# bitfury_10_1403.net
KiCad netlist of a schematic drawn in EAGLE
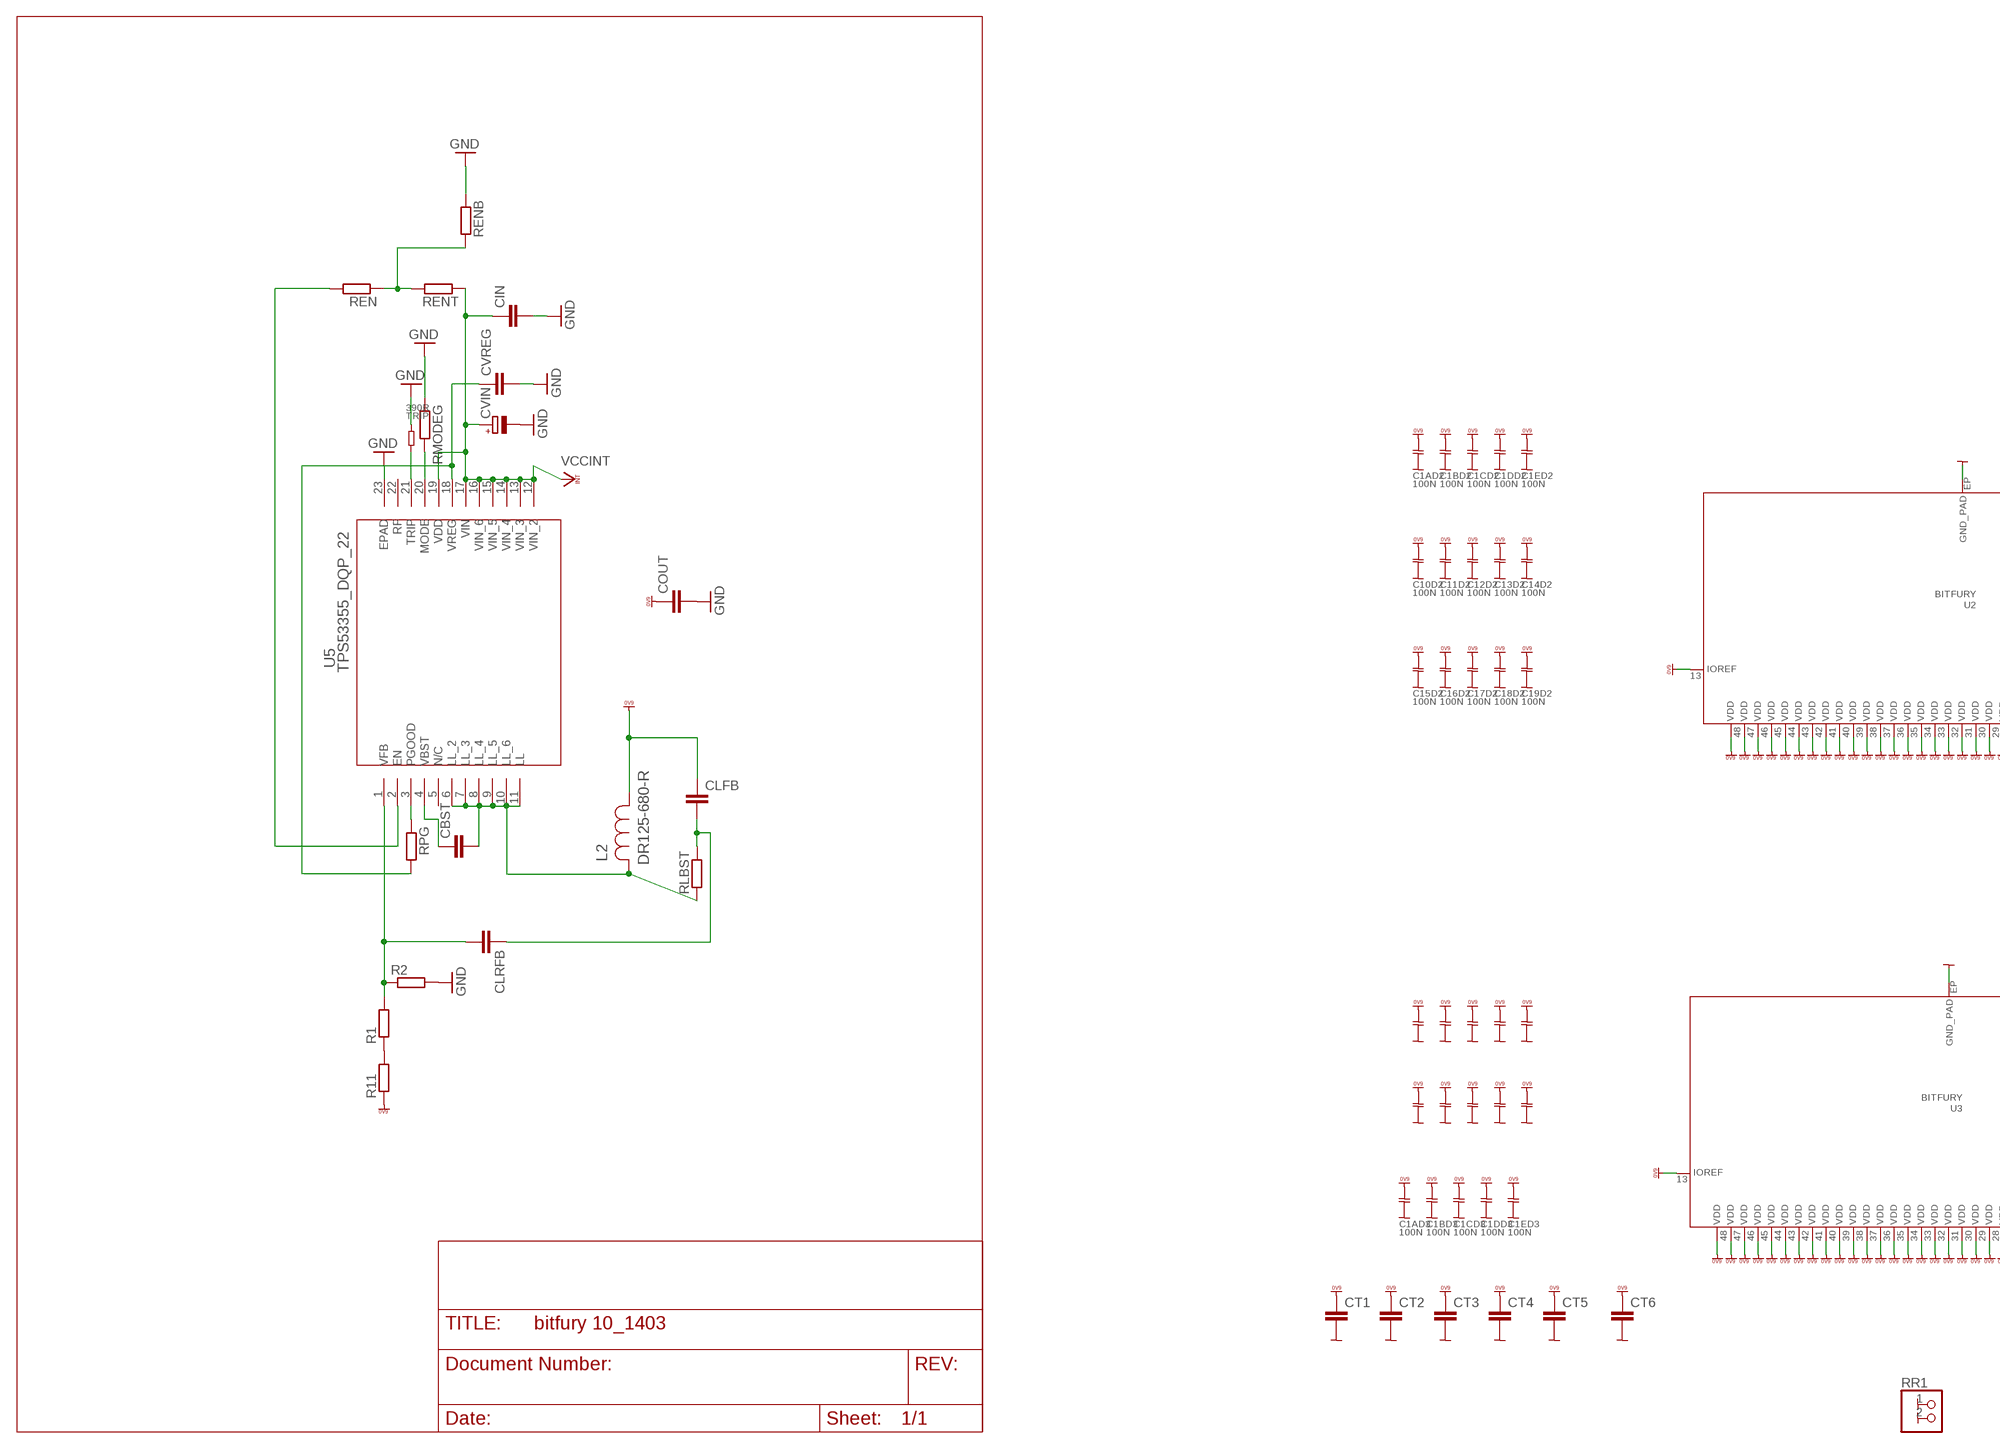
[diagram p0: schematic, sheet 1, part 1 of 3]
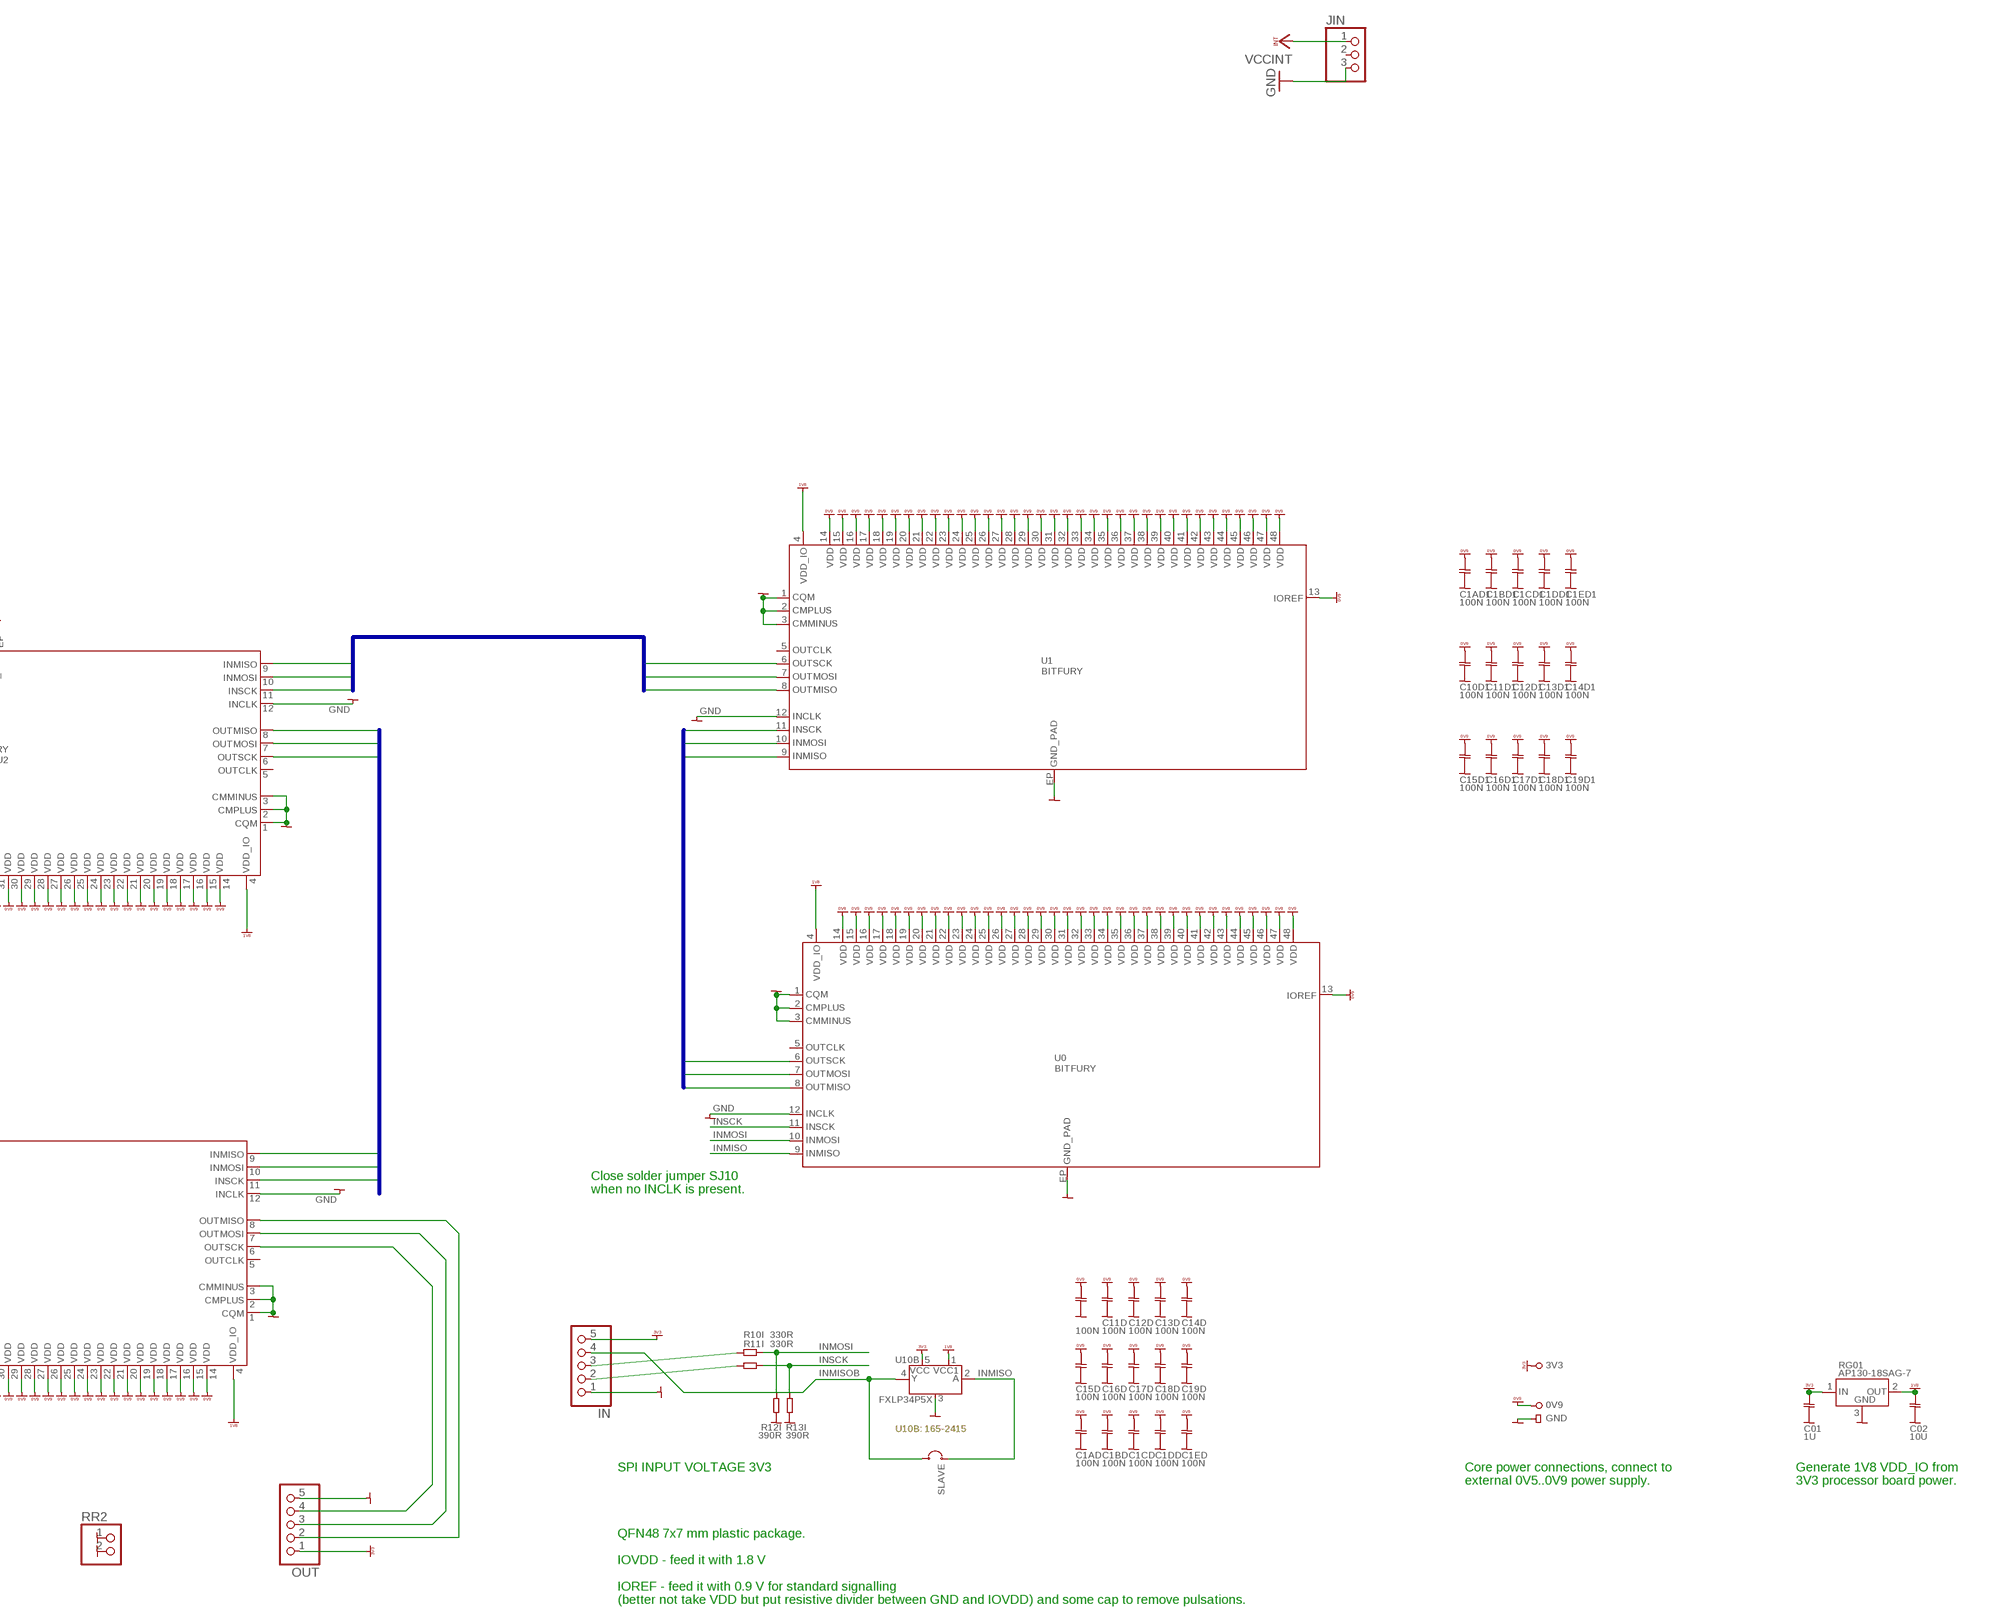
[diagram p1: schematic, sheet 1, part 2 of 3]
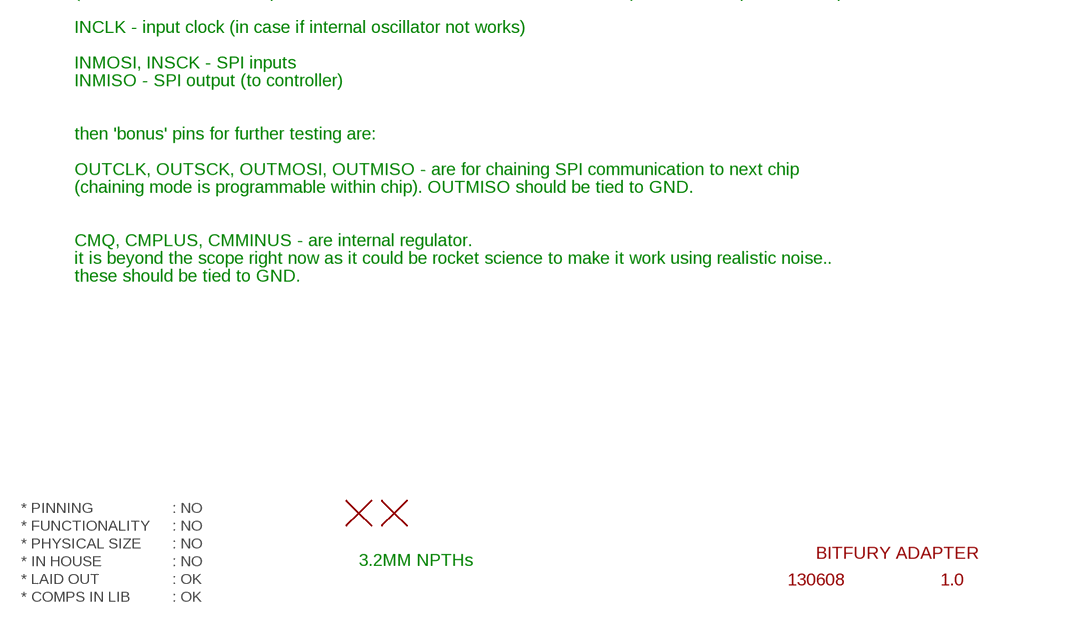
[diagram p2: schematic, sheet 1, part 3 of 3]

(export (version "E")
  (design (tool "Eeschema 10.0.6"))
  (components
    (comp (ref "0V9")
      (value "PIN_TEST_BIG")
      (footprint "eagle-import:PAD_HOLE_BIG")
      (libsource (lib "eagle-import") (part "PIN_TEST_BIG"))
    )
    (comp (ref "3V3")
      (value "PIN_TEST_BIG")
      (footprint "eagle-import:PAD_HOLE_BIG")
      (libsource (lib "eagle-import") (part "PIN_TEST_BIG"))
    )
    (comp (ref "C01")
      (value "1U")
      (footprint "eagle-import:CAP0603")
      (libsource (lib "eagle-import") (part "CAP0603"))
    )
    (comp (ref "C1AD")
      (value "100N")
      (footprint "eagle-import:CAP0402")
      (libsource (lib "eagle-import") (part "CAP0402"))
    )
    (comp (ref "C1AD1")
      (value "100N")
      (footprint "eagle-import:CAP0402")
      (libsource (lib "eagle-import") (part "CAP0402"))
    )
    (comp (ref "C1AD2")
      (value "100N")
      (footprint "eagle-import:CAP0402")
      (libsource (lib "eagle-import") (part "CAP0402"))
    )
    (comp (ref "C1AD3")
      (value "100N")
      (footprint "eagle-import:CAP0402")
      (libsource (lib "eagle-import") (part "CAP0402"))
    )
    (comp (ref "C1BD")
      (value "100N")
      (footprint "eagle-import:CAP0402")
      (libsource (lib "eagle-import") (part "CAP0402"))
    )
    (comp (ref "C1BD1")
      (value "100N")
      (footprint "eagle-import:CAP0402")
      (libsource (lib "eagle-import") (part "CAP0402"))
    )
    (comp (ref "C1BD2")
      (value "100N")
      (footprint "eagle-import:CAP0402")
      (libsource (lib "eagle-import") (part "CAP0402"))
    )
    (comp (ref "C1BD3")
      (value "100N")
      (footprint "eagle-import:CAP0402")
      (libsource (lib "eagle-import") (part "CAP0402"))
    )
    (comp (ref "C1CD")
      (value "100N")
      (footprint "eagle-import:CAP0402")
      (libsource (lib "eagle-import") (part "CAP0402"))
    )
    (comp (ref "C1CD1")
      (value "100N")
      (footprint "eagle-import:CAP0402")
      (libsource (lib "eagle-import") (part "CAP0402"))
    )
    (comp (ref "C1CD2")
      (value "100N")
      (footprint "eagle-import:CAP0402")
      (libsource (lib "eagle-import") (part "CAP0402"))
    )
    (comp (ref "C1CD3")
      (value "100N")
      (footprint "eagle-import:CAP0402")
      (libsource (lib "eagle-import") (part "CAP0402"))
    )
    (comp (ref "C1DD")
      (value "100N")
      (footprint "eagle-import:CAP0402")
      (libsource (lib "eagle-import") (part "CAP0402"))
    )
    (comp (ref "C1DD1")
      (value "100N")
      (footprint "eagle-import:CAP0402")
      (libsource (lib "eagle-import") (part "CAP0402"))
    )
    (comp (ref "C1DD2")
      (value "100N")
      (footprint "eagle-import:CAP0402")
      (libsource (lib "eagle-import") (part "CAP0402"))
    )
    (comp (ref "C1DD3")
      (value "100N")
      (footprint "eagle-import:CAP0402")
      (libsource (lib "eagle-import") (part "CAP0402"))
    )
    (comp (ref "C1ED")
      (value "100N")
      (footprint "eagle-import:CAP0402")
      (libsource (lib "eagle-import") (part "CAP0402"))
    )
    (comp (ref "C1ED1")
      (value "100N")
      (footprint "eagle-import:CAP0402")
      (libsource (lib "eagle-import") (part "CAP0402"))
    )
    (comp (ref "C1ED2")
      (value "100N")
      (footprint "eagle-import:CAP0402")
      (libsource (lib "eagle-import") (part "CAP0402"))
    )
    (comp (ref "C1ED3")
      (value "100N")
      (footprint "eagle-import:CAP0402")
      (libsource (lib "eagle-import") (part "CAP0402"))
    )
    (comp (ref "C02")
      (value "10U")
      (footprint "eagle-import:CAP0603")
      (libsource (lib "eagle-import") (part "CAP0603"))
    )
    (comp (ref "C10D")
      (value "100N")
      (footprint "eagle-import:CAP0402")
      (libsource (lib "eagle-import") (part "CAP0402"))
    )
    (comp (ref "C10D1")
      (value "100N")
      (footprint "eagle-import:CAP0402")
      (libsource (lib "eagle-import") (part "CAP0402"))
    )
    (comp (ref "C10D2")
      (value "100N")
      (footprint "eagle-import:CAP0402")
      (libsource (lib "eagle-import") (part "CAP0402"))
    )
    (comp (ref "C10D3")
      (value "100N")
      (footprint "eagle-import:CAP0402")
      (libsource (lib "eagle-import") (part "CAP0402"))
    )
    (comp (ref "C11D")
      (value "100N")
      (footprint "eagle-import:CAP0402")
      (libsource (lib "eagle-import") (part "CAP0402"))
    )
    (comp (ref "C11D1")
      (value "100N")
      (footprint "eagle-import:CAP0402")
      (libsource (lib "eagle-import") (part "CAP0402"))
    )
    (comp (ref "C11D2")
      (value "100N")
      (footprint "eagle-import:CAP0402")
      (libsource (lib "eagle-import") (part "CAP0402"))
    )
    (comp (ref "C11D3")
      (value "100N")
      (footprint "eagle-import:CAP0402")
      (libsource (lib "eagle-import") (part "CAP0402"))
    )
    (comp (ref "C12D")
      (value "100N")
      (footprint "eagle-import:CAP0402")
      (libsource (lib "eagle-import") (part "CAP0402"))
    )
    (comp (ref "C12D1")
      (value "100N")
      (footprint "eagle-import:CAP0402")
      (libsource (lib "eagle-import") (part "CAP0402"))
    )
    (comp (ref "C12D2")
      (value "100N")
      (footprint "eagle-import:CAP0402")
      (libsource (lib "eagle-import") (part "CAP0402"))
    )
    (comp (ref "C12D3")
      (value "100N")
      (footprint "eagle-import:CAP0402")
      (libsource (lib "eagle-import") (part "CAP0402"))
    )
    (comp (ref "C13D")
      (value "100N")
      (footprint "eagle-import:CAP0402")
      (libsource (lib "eagle-import") (part "CAP0402"))
    )
    (comp (ref "C13D1")
      (value "100N")
      (footprint "eagle-import:CAP0402")
      (libsource (lib "eagle-import") (part "CAP0402"))
    )
    (comp (ref "C13D2")
      (value "100N")
      (footprint "eagle-import:CAP0402")
      (libsource (lib "eagle-import") (part "CAP0402"))
    )
    (comp (ref "C13D3")
      (value "100N")
      (footprint "eagle-import:CAP0402")
      (libsource (lib "eagle-import") (part "CAP0402"))
    )
    (comp (ref "C14D")
      (value "100N")
      (footprint "eagle-import:CAP0402")
      (libsource (lib "eagle-import") (part "CAP0402"))
    )
    (comp (ref "C14D1")
      (value "100N")
      (footprint "eagle-import:CAP0402")
      (libsource (lib "eagle-import") (part "CAP0402"))
    )
    (comp (ref "C14D2")
      (value "100N")
      (footprint "eagle-import:CAP0402")
      (libsource (lib "eagle-import") (part "CAP0402"))
    )
    (comp (ref "C14D3")
      (value "100N")
      (footprint "eagle-import:CAP0402")
      (libsource (lib "eagle-import") (part "CAP0402"))
    )
    (comp (ref "C15D")
      (value "100N")
      (footprint "eagle-import:CAP0402")
      (libsource (lib "eagle-import") (part "CAP0402"))
    )
    (comp (ref "C15D1")
      (value "100N")
      (footprint "eagle-import:CAP0402")
      (libsource (lib "eagle-import") (part "CAP0402"))
    )
    (comp (ref "C15D2")
      (value "100N")
      (footprint "eagle-import:CAP0402")
      (libsource (lib "eagle-import") (part "CAP0402"))
    )
    (comp (ref "C15D3")
      (value "100N")
      (footprint "eagle-import:CAP0402")
      (libsource (lib "eagle-import") (part "CAP0402"))
    )
    (comp (ref "C16D")
      (value "100N")
      (footprint "eagle-import:CAP0402")
      (libsource (lib "eagle-import") (part "CAP0402"))
    )
    (comp (ref "C16D1")
      (value "100N")
      (footprint "eagle-import:CAP0402")
      (libsource (lib "eagle-import") (part "CAP0402"))
    )
    (comp (ref "C16D2")
      (value "100N")
      (footprint "eagle-import:CAP0402")
      (libsource (lib "eagle-import") (part "CAP0402"))
    )
    (comp (ref "C16D3")
      (value "100N")
      (footprint "eagle-import:CAP0402")
      (libsource (lib "eagle-import") (part "CAP0402"))
    )
    (comp (ref "C17D")
      (value "100N")
      (footprint "eagle-import:CAP0402")
      (libsource (lib "eagle-import") (part "CAP0402"))
    )
    (comp (ref "C17D1")
      (value "100N")
      (footprint "eagle-import:CAP0402")
      (libsource (lib "eagle-import") (part "CAP0402"))
    )
    (comp (ref "C17D2")
      (value "100N")
      (footprint "eagle-import:CAP0402")
      (libsource (lib "eagle-import") (part "CAP0402"))
    )
    (comp (ref "C17D3")
      (value "100N")
      (footprint "eagle-import:CAP0402")
      (libsource (lib "eagle-import") (part "CAP0402"))
    )
    (comp (ref "C18D")
      (value "100N")
      (footprint "eagle-import:CAP0402")
      (libsource (lib "eagle-import") (part "CAP0402"))
    )
    (comp (ref "C18D1")
      (value "100N")
      (footprint "eagle-import:CAP0402")
      (libsource (lib "eagle-import") (part "CAP0402"))
    )
    (comp (ref "C18D2")
      (value "100N")
      (footprint "eagle-import:CAP0402")
      (libsource (lib "eagle-import") (part "CAP0402"))
    )
    (comp (ref "C18D3")
      (value "100N")
      (footprint "eagle-import:CAP0402")
      (libsource (lib "eagle-import") (part "CAP0402"))
    )
    (comp (ref "C19D")
      (value "100N")
      (footprint "eagle-import:CAP0402")
      (libsource (lib "eagle-import") (part "CAP0402"))
    )
    (comp (ref "C19D1")
      (value "100N")
      (footprint "eagle-import:CAP0402")
      (libsource (lib "eagle-import") (part "CAP0402"))
    )
    (comp (ref "C19D2")
      (value "100N")
      (footprint "eagle-import:CAP0402")
      (libsource (lib "eagle-import") (part "CAP0402"))
    )
    (comp (ref "C19D3")
      (value "100N")
      (footprint "eagle-import:CAP0402")
      (libsource (lib "eagle-import") (part "CAP0402"))
    )
    (comp (ref "CBST")
      (value "C-EUC0805")
      (footprint "eagle-import:C0805")
      (libsource (lib "eagle-import") (part "C-EUC0805"))
    )
    (comp (ref "CIN")
      (value "C-EUC1210")
      (footprint "eagle-import:C1210")
      (libsource (lib "eagle-import") (part "C-EUC1210"))
    )
    (comp (ref "CLFB")
      (value "C-EUC0805")
      (footprint "eagle-import:C0805")
      (libsource (lib "eagle-import") (part "C-EUC0805"))
    )
    (comp (ref "CLRFB")
      (value "C-EUC0805")
      (footprint "eagle-import:C0805")
      (libsource (lib "eagle-import") (part "C-EUC0805"))
    )
    (comp (ref "COUT")
      (value "C-EUC1210")
      (footprint "eagle-import:C1210")
      (libsource (lib "eagle-import") (part "C-EUC1210"))
    )
    (comp (ref "CT1")
      (value "C-EUC1206")
      (footprint "eagle-import:C1206")
      (libsource (lib "eagle-import") (part "C-EUC1206"))
    )
    (comp (ref "CT2")
      (value "C-EUC1206")
      (footprint "eagle-import:C1206")
      (libsource (lib "eagle-import") (part "C-EUC1206"))
    )
    (comp (ref "CT3")
      (value "C-EUC1206")
      (footprint "eagle-import:C1206")
      (libsource (lib "eagle-import") (part "C-EUC1206"))
    )
    (comp (ref "CT4")
      (value "C-EUC1206")
      (footprint "eagle-import:C1206")
      (libsource (lib "eagle-import") (part "C-EUC1206"))
    )
    (comp (ref "CT5")
      (value "C-EUC1206")
      (footprint "eagle-import:C1206")
      (libsource (lib "eagle-import") (part "C-EUC1206"))
    )
    (comp (ref "CT6")
      (value "C-EUC1206")
      (footprint "eagle-import:C1206")
      (libsource (lib "eagle-import") (part "C-EUC1206"))
    )
    (comp (ref "CVIN")
      (value "CPOL-EU153CLV-0505")
      (footprint "eagle-import:153CLV-0505")
      (libsource (lib "eagle-import") (part "CPOL-EU153CLV-0505"))
    )
    (comp (ref "CVREG")
      (value "C-EUC0603")
      (footprint "eagle-import:C0603")
      (libsource (lib "eagle-import") (part "C-EUC0603"))
    )
    (comp (ref "H1")
      (value "HOLE_NPTH_3.2MM")
      (footprint "eagle-import:HOLE_NPTH_3.2MM")
      (libsource (lib "eagle-import") (part "HOLE_NPTH_3.2MM"))
    )
    (comp (ref "H2")
      (value "HOLE_NPTH_3.2MM")
      (footprint "eagle-import:HOLE_NPTH_3.2MM")
      (libsource (lib "eagle-import") (part "HOLE_NPTH_3.2MM"))
    )
    (comp (ref "IN")
      (value "PINHD-1X5/90")
      (footprint "eagle-import:1X05_90")
      (libsource (lib "eagle-import") (part "PINHD-1X5/90"))
    )
    (comp (ref "JIN")
      (value "PINHD-1X3")
      (footprint "eagle-import:1X03")
      (libsource (lib "eagle-import") (part "PINHD-1X3"))
    )
    (comp (ref "L2")
      (value "DR125-680-R")
      (footprint "eagle-import:INDM125125X600N")
      (fields (field (name "TOLERANCE") "±20%"))
      (libsource (lib "eagle-import") (part "DR125-680-R"))
    )
    (comp (ref "OUT")
      (value "PINHD-1X5/90")
      (footprint "eagle-import:1X05_90")
      (libsource (lib "eagle-import") (part "PINHD-1X5/90"))
    )
    (comp (ref "R1")
      (value "R-EU_R0603")
      (footprint "eagle-import:R0603")
      (libsource (lib "eagle-import") (part "R-EU_R0603"))
    )
    (comp (ref "R2")
      (value "R-EU_R0603")
      (footprint "eagle-import:R0603")
      (libsource (lib "eagle-import") (part "R-EU_R0603"))
    )
    (comp (ref "R10I")
      (value "330R")
      (footprint "eagle-import:RES0603")
      (libsource (lib "eagle-import") (part "RES0603"))
    )
    (comp (ref "R11")
      (value "R-EU_R0603")
      (footprint "eagle-import:R0603")
      (libsource (lib "eagle-import") (part "R-EU_R0603"))
    )
    (comp (ref "R11I")
      (value "330R")
      (footprint "eagle-import:RES0603")
      (libsource (lib "eagle-import") (part "RES0603"))
    )
    (comp (ref "R12I")
      (value "390R")
      (footprint "eagle-import:RES0603")
      (libsource (lib "eagle-import") (part "RES0603"))
    )
    (comp (ref "R13I")
      (value "390R")
      (footprint "eagle-import:RES0603")
      (libsource (lib "eagle-import") (part "RES0603"))
    )
    (comp (ref "REN")
      (value "R-EU_R0603")
      (footprint "eagle-import:R0603")
      (libsource (lib "eagle-import") (part "R-EU_R0603"))
    )
    (comp (ref "RENB")
      (value "R-EU_R0603")
      (footprint "eagle-import:R0603")
      (libsource (lib "eagle-import") (part "R-EU_R0603"))
    )
    (comp (ref "RENT")
      (value "R-EU_R0603")
      (footprint "eagle-import:R0603")
      (libsource (lib "eagle-import") (part "R-EU_R0603"))
    )
    (comp (ref "RG01")
      (value "AP130-18SAG-7")
      (footprint "eagle-import:SOT23")
      (libsource (lib "eagle-import") (part "AP130-18SAG-7"))
    )
    (comp (ref "RLBST")
      (value "R-EU_R0603")
      (footprint "eagle-import:R0603")
      (libsource (lib "eagle-import") (part "R-EU_R0603"))
    )
    (comp (ref "RMODEG")
      (value "R-EU_R0603")
      (footprint "eagle-import:R0603")
      (libsource (lib "eagle-import") (part "R-EU_R0603"))
    )
    (comp (ref "RPG")
      (value "R-EU_R0603")
      (footprint "eagle-import:R0603")
      (libsource (lib "eagle-import") (part "R-EU_R0603"))
    )
    (comp (ref "RR1")
      (value "PINHD-1X2/90")
      (footprint "eagle-import:1X02_90")
      (libsource (lib "eagle-import") (part "PINHD-1X2/90"))
    )
    (comp (ref "RR2")
      (value "PINHD-1X2/90")
      (footprint "eagle-import:1X02_90")
      (libsource (lib "eagle-import") (part "PINHD-1X2/90"))
    )
    (comp (ref "SLAVE")
      (value "SJ2SJ2-S")
      (footprint "eagle-import:SJ2-S")
      (libsource (lib "eagle-import") (part "SJ2SJ2-S"))
    )
    (comp (ref "TRIP")
      (value "390R")
      (footprint "eagle-import:RES0603")
      (libsource (lib "eagle-import") (part "RES0603"))
    )
    (comp (ref "U$83")
      (value "PIN_GND")
      (footprint "eagle-import:PAD_HOLE_SQR_1.8MM")
      (libsource (lib "eagle-import") (part "PIN_GND"))
    )
    (comp (ref "U0")
      (value "BITFURY")
      (footprint "eagle-import:QNF48")
      (libsource (lib "eagle-import") (part "BITFURY"))
    )
    (comp (ref "U1")
      (value "BITFURY")
      (footprint "eagle-import:QNF48")
      (libsource (lib "eagle-import") (part "BITFURY"))
    )
    (comp (ref "U2")
      (value "BITFURY")
      (footprint "eagle-import:QNF48")
      (libsource (lib "eagle-import") (part "BITFURY"))
    )
    (comp (ref "U3")
      (value "BITFURY")
      (footprint "eagle-import:QNF48")
      (libsource (lib "eagle-import") (part "BITFURY"))
    )
    (comp (ref "U5")
      (value "TPS53355_DQP_22")
      (footprint "eagle-import:DQP22_5P479X3P24")
      (fields
        (field (name "GENERIC_PART_NUMBER") "TPS53355")
        (field (name "MANUFACTURER") "Texas Instruments")
        (field (name "MANUFACTURER_PART_NUMBER") "tps53355_dqp_22")
      )
      (libsource (lib "eagle-import") (part "TPS53355_DQP_22"))
    )
    (comp (ref "U10B")
      (value "FXLP34P5X")
      (footprint "eagle-import:SOT23-5")
      (libsource (lib "eagle-import") (part "FXLP34P5X"))
    )
  )
  (nets
    (net (code "1") (name "/B1B2C1") (class "Default")
      (node (ref "U0") (pin "6") (pinfunction "6.OUTSCK_6") (pintype "input"))
      (node (ref "U1") (pin "11") (pinfunction "11.INSCK_11") (pintype "input"))
    )
    (net (code "2") (name "/B1B2C2") (class "Default")
      (node (ref "U0") (pin "7") (pinfunction "7.OUTMOSI_7") (pintype "output"))
      (node (ref "U1") (pin "10") (pinfunction "10.INMOSI_10") (pintype "output"))
    )
    (net (code "3") (name "/B1B2C3") (class "Default")
      (node (ref "U0") (pin "8") (pinfunction "8.OUTMISO_8") (pintype "output"))
      (node (ref "U1") (pin "9") (pinfunction "9.INMISO_9") (pintype "output"))
    )
    (net (code "4") (name "/B2B3C1") (class "Default")
      (node (ref "U1") (pin "6") (pinfunction "6.OUTSCK_6") (pintype "input"))
      (node (ref "U2") (pin "11") (pinfunction "11.INSCK_11") (pintype "input"))
    )
    (net (code "5") (name "/B2B3C2") (class "Default")
      (node (ref "U1") (pin "7") (pinfunction "7.OUTMOSI_7") (pintype "output"))
      (node (ref "U2") (pin "10") (pinfunction "10.INMOSI_10") (pintype "output"))
    )
    (net (code "6") (name "/B2B3C3") (class "Default")
      (node (ref "U1") (pin "8") (pinfunction "8.OUTMISO_8") (pintype "output"))
      (node (ref "U2") (pin "9") (pinfunction "9.INMISO_9") (pintype "output"))
    )
    (net (code "7") (name "/B3B4C1") (class "Default")
      (node (ref "U2") (pin "6") (pinfunction "6.OUTSCK_6") (pintype "input"))
      (node (ref "U3") (pin "11") (pinfunction "11.INSCK_11") (pintype "input"))
    )
    (net (code "8") (name "/B3B4C2") (class "Default")
      (node (ref "U2") (pin "7") (pinfunction "7.OUTMOSI_7") (pintype "output"))
      (node (ref "U3") (pin "10") (pinfunction "10.INMOSI_10") (pintype "output"))
    )
    (net (code "9") (name "/B3B4C3") (class "Default")
      (node (ref "U2") (pin "8") (pinfunction "8.OUTMISO_8") (pintype "output"))
      (node (ref "U3") (pin "9") (pinfunction "9.INMISO_9") (pintype "output"))
    )
    (net (code "10") (name "/INMISO") (class "Default")
      (node (ref "SLAVE") (pin "2") (pinfunction "P$2_2") (pintype "passive"))
      (node (ref "U0") (pin "9") (pinfunction "9.INMISO_9") (pintype "output"))
      (node (ref "U10B") (pin "2") (pinfunction "2.A_2") (pintype "passive"))
    )
    (net (code "11") (name "/INMISOB") (class "Default")
      (node (ref "IN") (pin "4") (pinfunction "4_4") (pintype "passive"))
      (node (ref "SLAVE") (pin "1") (pinfunction "P$1_1") (pintype "passive"))
      (node (ref "U10B") (pin "4") (pinfunction "4.Y_4") (pintype "passive"))
    )
    (net (code "12") (name "/INMOSI") (class "Default")
      (node (ref "R10I") (pin "2") (pinfunction "2_2") (pintype "passive"))
      (node (ref "R12I") (pin "2") (pinfunction "2_2") (pintype "passive"))
      (node (ref "U0") (pin "10") (pinfunction "10.INMOSI_10") (pintype "output"))
    )
    (net (code "13") (name "/INSCK") (class "Default")
      (node (ref "R11I") (pin "2") (pinfunction "2_2") (pintype "passive"))
      (node (ref "R13I") (pin "2") (pinfunction "2_2") (pintype "passive"))
      (node (ref "U0") (pin "11") (pinfunction "11.INSCK_11") (pintype "input"))
    )
    (net (code "14") (name "GND") (class "Default")
      (node (ref "C01") (pin "2") (pinfunction "2_2") (pintype "passive"))
      (node (ref "C02") (pin "2") (pinfunction "2_2") (pintype "passive"))
      (node (ref "C10D") (pin "2") (pinfunction "2_2") (pintype "passive"))
      (node (ref "C10D1") (pin "2") (pinfunction "2_2") (pintype "passive"))
      (node (ref "C10D2") (pin "2") (pinfunction "2_2") (pintype "passive"))
      (node (ref "C10D3") (pin "2") (pinfunction "2_2") (pintype "passive"))
      (node (ref "C11D") (pin "2") (pinfunction "2_2") (pintype "passive"))
      (node (ref "C11D1") (pin "2") (pinfunction "2_2") (pintype "passive"))
      (node (ref "C11D2") (pin "2") (pinfunction "2_2") (pintype "passive"))
      (node (ref "C11D3") (pin "2") (pinfunction "2_2") (pintype "passive"))
      (node (ref "C12D") (pin "2") (pinfunction "2_2") (pintype "passive"))
      (node (ref "C12D1") (pin "2") (pinfunction "2_2") (pintype "passive"))
      (node (ref "C12D2") (pin "2") (pinfunction "2_2") (pintype "passive"))
      (node (ref "C12D3") (pin "2") (pinfunction "2_2") (pintype "passive"))
      (node (ref "C13D") (pin "2") (pinfunction "2_2") (pintype "passive"))
      (node (ref "C13D1") (pin "2") (pinfunction "2_2") (pintype "passive"))
      (node (ref "C13D2") (pin "2") (pinfunction "2_2") (pintype "passive"))
      (node (ref "C13D3") (pin "2") (pinfunction "2_2") (pintype "passive"))
      (node (ref "C14D") (pin "2") (pinfunction "2_2") (pintype "passive"))
      (node (ref "C14D1") (pin "2") (pinfunction "2_2") (pintype "passive"))
      (node (ref "C14D2") (pin "2") (pinfunction "2_2") (pintype "passive"))
      (node (ref "C14D3") (pin "2") (pinfunction "2_2") (pintype "passive"))
      (node (ref "C15D") (pin "2") (pinfunction "2_2") (pintype "passive"))
      (node (ref "C15D1") (pin "2") (pinfunction "2_2") (pintype "passive"))
      (node (ref "C15D2") (pin "2") (pinfunction "2_2") (pintype "passive"))
      (node (ref "C15D3") (pin "2") (pinfunction "2_2") (pintype "passive"))
      (node (ref "C16D") (pin "2") (pinfunction "2_2") (pintype "passive"))
      (node (ref "C16D1") (pin "2") (pinfunction "2_2") (pintype "passive"))
      (node (ref "C16D2") (pin "2") (pinfunction "2_2") (pintype "passive"))
      (node (ref "C16D3") (pin "2") (pinfunction "2_2") (pintype "passive"))
      (node (ref "C17D") (pin "2") (pinfunction "2_2") (pintype "passive"))
      (node (ref "C17D1") (pin "2") (pinfunction "2_2") (pintype "passive"))
      (node (ref "C17D2") (pin "2") (pinfunction "2_2") (pintype "passive"))
      (node (ref "C17D3") (pin "2") (pinfunction "2_2") (pintype "passive"))
      (node (ref "C18D") (pin "2") (pinfunction "2_2") (pintype "passive"))
      (node (ref "C18D1") (pin "2") (pinfunction "2_2") (pintype "passive"))
      (node (ref "C18D2") (pin "2") (pinfunction "2_2") (pintype "passive"))
      (node (ref "C18D3") (pin "2") (pinfunction "2_2") (pintype "passive"))
      (node (ref "C19D") (pin "2") (pinfunction "2_2") (pintype "passive"))
      (node (ref "C19D1") (pin "2") (pinfunction "2_2") (pintype "passive"))
      (node (ref "C19D2") (pin "2") (pinfunction "2_2") (pintype "passive"))
      (node (ref "C19D3") (pin "2") (pinfunction "2_2") (pintype "passive"))
      (node (ref "C1AD") (pin "2") (pinfunction "2_2") (pintype "passive"))
      (node (ref "C1AD1") (pin "2") (pinfunction "2_2") (pintype "passive"))
      (node (ref "C1AD2") (pin "2") (pinfunction "2_2") (pintype "passive"))
      (node (ref "C1AD3") (pin "2") (pinfunction "2_2") (pintype "passive"))
      (node (ref "C1BD") (pin "2") (pinfunction "2_2") (pintype "passive"))
      (node (ref "C1BD1") (pin "2") (pinfunction "2_2") (pintype "passive"))
      (node (ref "C1BD2") (pin "2") (pinfunction "2_2") (pintype "passive"))
      (node (ref "C1BD3") (pin "2") (pinfunction "2_2") (pintype "passive"))
      (node (ref "C1CD") (pin "2") (pinfunction "2_2") (pintype "passive"))
      (node (ref "C1CD1") (pin "2") (pinfunction "2_2") (pintype "passive"))
      (node (ref "C1CD2") (pin "2") (pinfunction "2_2") (pintype "passive"))
      (node (ref "C1CD3") (pin "2") (pinfunction "2_2") (pintype "passive"))
      (node (ref "C1DD") (pin "2") (pinfunction "2_2") (pintype "passive"))
      (node (ref "C1DD1") (pin "2") (pinfunction "2_2") (pintype "passive"))
      (node (ref "C1DD2") (pin "2") (pinfunction "2_2") (pintype "passive"))
      (node (ref "C1DD3") (pin "2") (pinfunction "2_2") (pintype "passive"))
      (node (ref "C1ED") (pin "2") (pinfunction "2_2") (pintype "passive"))
      (node (ref "C1ED1") (pin "2") (pinfunction "2_2") (pintype "passive"))
      (node (ref "C1ED2") (pin "2") (pinfunction "2_2") (pintype "passive"))
      (node (ref "C1ED3") (pin "2") (pinfunction "2_2") (pintype "passive"))
      (node (ref "CIN") (pin "2") (pinfunction "2_2") (pintype "passive"))
      (node (ref "COUT") (pin "2") (pinfunction "2_2") (pintype "passive"))
      (node (ref "CT1") (pin "2") (pinfunction "2_2") (pintype "passive"))
      (node (ref "CT2") (pin "2") (pinfunction "2_2") (pintype "passive"))
      (node (ref "CT3") (pin "2") (pinfunction "2_2") (pintype "passive"))
      (node (ref "CT4") (pin "2") (pinfunction "2_2") (pintype "passive"))
      (node (ref "CT5") (pin "2") (pinfunction "2_2") (pintype "passive"))
      (node (ref "CT6") (pin "2") (pinfunction "2_2") (pintype "passive"))
      (node (ref "CVIN") (pin "-") (pinfunction "-_-") (pintype "passive"))
      (node (ref "CVREG") (pin "2") (pinfunction "2_2") (pintype "passive"))
      (node (ref "IN") (pin "1") (pinfunction "1_1") (pintype "passive"))
      (node (ref "JIN") (pin "3") (pinfunction "3_3") (pintype "passive"))
      (node (ref "OUT") (pin "5") (pinfunction "5_5") (pintype "passive"))
      (node (ref "R12I") (pin "1") (pinfunction "1_1") (pintype "passive"))
      (node (ref "R13I") (pin "1") (pinfunction "1_1") (pintype "passive"))
      (node (ref "R2") (pin "2") (pinfunction "2_2") (pintype "passive"))
      (node (ref "RENB") (pin "1") (pinfunction "1_1") (pintype "passive"))
      (node (ref "RG01") (pin "3") (pinfunction "3.GND_3") (pintype "passive"))
      (node (ref "RMODEG") (pin "1") (pinfunction "1_1") (pintype "passive"))
      (node (ref "RR1") (pin "1") (pinfunction "1_1") (pintype "passive"))
      (node (ref "RR1") (pin "2") (pinfunction "2_2") (pintype "passive"))
      (node (ref "RR2") (pin "1") (pinfunction "1_1") (pintype "passive"))
      (node (ref "RR2") (pin "2") (pinfunction "2_2") (pintype "passive"))
      (node (ref "TRIP") (pin "1") (pinfunction "1_1") (pintype "passive"))
      (node (ref "U$83") (pin "1") (pinfunction "P$1_1") (pintype "passive"))
      (node (ref "U0") (pin "1") (pinfunction "1.QCM_1") (pintype "bidirectional"))
      (node (ref "U0") (pin "12") (pinfunction "12.INCLK_12") (pintype "output"))
      (node (ref "U0") (pin "2") (pinfunction "2.CMPLUS_2") (pintype "passive"))
      (node (ref "U0") (pin "3") (pinfunction "3.CMMINUS_3") (pintype "passive"))
      (node (ref "U0") (pin "EP") (pinfunction "EP.VSS_EP_EP") (pintype "passive"))
      (node (ref "U0") (pin "V1") (pinfunction "EP.VSS_EP_V1") (pintype "passive"))
      (node (ref "U0") (pin "V10") (pinfunction "EP.VSS_EP_V10") (pintype "passive"))
      (node (ref "U0") (pin "V11") (pinfunction "EP.VSS_EP_V11") (pintype "passive"))
      (node (ref "U0") (pin "V12") (pinfunction "EP.VSS_EP_V12") (pintype "passive"))
      (node (ref "U0") (pin "V13") (pinfunction "EP.VSS_EP_V13") (pintype "passive"))
      (node (ref "U0") (pin "V14") (pinfunction "EP.VSS_EP_V14") (pintype "passive"))
      (node (ref "U0") (pin "V15") (pinfunction "EP.VSS_EP_V15") (pintype "passive"))
      (node (ref "U0") (pin "V16") (pinfunction "EP.VSS_EP_V16") (pintype "passive"))
      (node (ref "U0") (pin "V17") (pinfunction "EP.VSS_EP_V17") (pintype "passive"))
      (node (ref "U0") (pin "V18") (pinfunction "EP.VSS_EP_V18") (pintype "passive"))
      (node (ref "U0") (pin "V19") (pinfunction "EP.VSS_EP_V19") (pintype "passive"))
      (node (ref "U0") (pin "V2") (pinfunction "EP.VSS_EP_V2") (pintype "passive"))
      (node (ref "U0") (pin "V20") (pinfunction "EP.VSS_EP_V20") (pintype "passive"))
      (node (ref "U0") (pin "V21") (pinfunction "EP.VSS_EP_V21") (pintype "passive"))
      (node (ref "U0") (pin "V22") (pinfunction "EP.VSS_EP_V22") (pintype "passive"))
      (node (ref "U0") (pin "V23") (pinfunction "EP.VSS_EP_V23") (pintype "passive"))
      (node (ref "U0") (pin "V24") (pinfunction "EP.VSS_EP_V24") (pintype "passive"))
      (node (ref "U0") (pin "V25") (pinfunction "EP.VSS_EP_V25") (pintype "passive"))
      (node (ref "U0") (pin "V3") (pinfunction "EP.VSS_EP_V3") (pintype "passive"))
      (node (ref "U0") (pin "V4") (pinfunction "EP.VSS_EP_V4") (pintype "passive"))
      (node (ref "U0") (pin "V5") (pinfunction "EP.VSS_EP_V5") (pintype "passive"))
      (node (ref "U0") (pin "V6") (pinfunction "EP.VSS_EP_V6") (pintype "passive"))
      (node (ref "U0") (pin "V7") (pinfunction "EP.VSS_EP_V7") (pintype "passive"))
      (node (ref "U0") (pin "V8") (pinfunction "EP.VSS_EP_V8") (pintype "passive"))
      (node (ref "U0") (pin "V9") (pinfunction "EP.VSS_EP_V9") (pintype "passive"))
      (node (ref "U1") (pin "1") (pinfunction "1.QCM_1") (pintype "bidirectional"))
      (node (ref "U1") (pin "12") (pinfunction "12.INCLK_12") (pintype "output"))
      (node (ref "U1") (pin "2") (pinfunction "2.CMPLUS_2") (pintype "passive"))
      (node (ref "U1") (pin "3") (pinfunction "3.CMMINUS_3") (pintype "passive"))
      (node (ref "U1") (pin "EP") (pinfunction "EP.VSS_EP_EP") (pintype "passive"))
      (node (ref "U1") (pin "V1") (pinfunction "EP.VSS_EP_V1") (pintype "passive"))
      (node (ref "U1") (pin "V10") (pinfunction "EP.VSS_EP_V10") (pintype "passive"))
      (node (ref "U1") (pin "V11") (pinfunction "EP.VSS_EP_V11") (pintype "passive"))
      (node (ref "U1") (pin "V12") (pinfunction "EP.VSS_EP_V12") (pintype "passive"))
      (node (ref "U1") (pin "V13") (pinfunction "EP.VSS_EP_V13") (pintype "passive"))
      (node (ref "U1") (pin "V14") (pinfunction "EP.VSS_EP_V14") (pintype "passive"))
      (node (ref "U1") (pin "V15") (pinfunction "EP.VSS_EP_V15") (pintype "passive"))
      (node (ref "U1") (pin "V16") (pinfunction "EP.VSS_EP_V16") (pintype "passive"))
      (node (ref "U1") (pin "V17") (pinfunction "EP.VSS_EP_V17") (pintype "passive"))
      (node (ref "U1") (pin "V18") (pinfunction "EP.VSS_EP_V18") (pintype "passive"))
      (node (ref "U1") (pin "V19") (pinfunction "EP.VSS_EP_V19") (pintype "passive"))
      (node (ref "U1") (pin "V2") (pinfunction "EP.VSS_EP_V2") (pintype "passive"))
      (node (ref "U1") (pin "V20") (pinfunction "EP.VSS_EP_V20") (pintype "passive"))
      (node (ref "U1") (pin "V21") (pinfunction "EP.VSS_EP_V21") (pintype "passive"))
      (node (ref "U1") (pin "V22") (pinfunction "EP.VSS_EP_V22") (pintype "passive"))
      (node (ref "U1") (pin "V23") (pinfunction "EP.VSS_EP_V23") (pintype "passive"))
      (node (ref "U1") (pin "V24") (pinfunction "EP.VSS_EP_V24") (pintype "passive"))
      (node (ref "U1") (pin "V25") (pinfunction "EP.VSS_EP_V25") (pintype "passive"))
      (node (ref "U1") (pin "V3") (pinfunction "EP.VSS_EP_V3") (pintype "passive"))
      (node (ref "U1") (pin "V4") (pinfunction "EP.VSS_EP_V4") (pintype "passive"))
      (node (ref "U1") (pin "V5") (pinfunction "EP.VSS_EP_V5") (pintype "passive"))
      (node (ref "U1") (pin "V6") (pinfunction "EP.VSS_EP_V6") (pintype "passive"))
      (node (ref "U1") (pin "V7") (pinfunction "EP.VSS_EP_V7") (pintype "passive"))
      (node (ref "U1") (pin "V8") (pinfunction "EP.VSS_EP_V8") (pintype "passive"))
      (node (ref "U1") (pin "V9") (pinfunction "EP.VSS_EP_V9") (pintype "passive"))
      (node (ref "U10B") (pin "3") (pinfunction "3.GND_3") (pintype "passive"))
      (node (ref "U2") (pin "1") (pinfunction "1.QCM_1") (pintype "bidirectional"))
      (node (ref "U2") (pin "12") (pinfunction "12.INCLK_12") (pintype "output"))
      (node (ref "U2") (pin "2") (pinfunction "2.CMPLUS_2") (pintype "passive"))
      (node (ref "U2") (pin "3") (pinfunction "3.CMMINUS_3") (pintype "passive"))
      (node (ref "U2") (pin "EP") (pinfunction "EP.VSS_EP_EP") (pintype "passive"))
      (node (ref "U2") (pin "V1") (pinfunction "EP.VSS_EP_V1") (pintype "passive"))
      (node (ref "U2") (pin "V10") (pinfunction "EP.VSS_EP_V10") (pintype "passive"))
      (node (ref "U2") (pin "V11") (pinfunction "EP.VSS_EP_V11") (pintype "passive"))
      (node (ref "U2") (pin "V12") (pinfunction "EP.VSS_EP_V12") (pintype "passive"))
      (node (ref "U2") (pin "V13") (pinfunction "EP.VSS_EP_V13") (pintype "passive"))
      (node (ref "U2") (pin "V14") (pinfunction "EP.VSS_EP_V14") (pintype "passive"))
      (node (ref "U2") (pin "V15") (pinfunction "EP.VSS_EP_V15") (pintype "passive"))
      (node (ref "U2") (pin "V16") (pinfunction "EP.VSS_EP_V16") (pintype "passive"))
      (node (ref "U2") (pin "V17") (pinfunction "EP.VSS_EP_V17") (pintype "passive"))
      (node (ref "U2") (pin "V18") (pinfunction "EP.VSS_EP_V18") (pintype "passive"))
      (node (ref "U2") (pin "V19") (pinfunction "EP.VSS_EP_V19") (pintype "passive"))
      (node (ref "U2") (pin "V2") (pinfunction "EP.VSS_EP_V2") (pintype "passive"))
      (node (ref "U2") (pin "V20") (pinfunction "EP.VSS_EP_V20") (pintype "passive"))
      (node (ref "U2") (pin "V21") (pinfunction "EP.VSS_EP_V21") (pintype "passive"))
      (node (ref "U2") (pin "V22") (pinfunction "EP.VSS_EP_V22") (pintype "passive"))
      (node (ref "U2") (pin "V23") (pinfunction "EP.VSS_EP_V23") (pintype "passive"))
      (node (ref "U2") (pin "V24") (pinfunction "EP.VSS_EP_V24") (pintype "passive"))
      (node (ref "U2") (pin "V25") (pinfunction "EP.VSS_EP_V25") (pintype "passive"))
      (node (ref "U2") (pin "V3") (pinfunction "EP.VSS_EP_V3") (pintype "passive"))
      (node (ref "U2") (pin "V4") (pinfunction "EP.VSS_EP_V4") (pintype "passive"))
      (node (ref "U2") (pin "V5") (pinfunction "EP.VSS_EP_V5") (pintype "passive"))
      (node (ref "U2") (pin "V6") (pinfunction "EP.VSS_EP_V6") (pintype "passive"))
      (node (ref "U2") (pin "V7") (pinfunction "EP.VSS_EP_V7") (pintype "passive"))
      (node (ref "U2") (pin "V8") (pinfunction "EP.VSS_EP_V8") (pintype "passive"))
      (node (ref "U2") (pin "V9") (pinfunction "EP.VSS_EP_V9") (pintype "passive"))
      (node (ref "U3") (pin "1") (pinfunction "1.QCM_1") (pintype "bidirectional"))
      (node (ref "U3") (pin "12") (pinfunction "12.INCLK_12") (pintype "output"))
      (node (ref "U3") (pin "2") (pinfunction "2.CMPLUS_2") (pintype "passive"))
      (node (ref "U3") (pin "3") (pinfunction "3.CMMINUS_3") (pintype "passive"))
      (node (ref "U3") (pin "EP") (pinfunction "EP.VSS_EP_EP") (pintype "passive"))
      (node (ref "U3") (pin "V1") (pinfunction "EP.VSS_EP_V1") (pintype "passive"))
      (node (ref "U3") (pin "V10") (pinfunction "EP.VSS_EP_V10") (pintype "passive"))
      (node (ref "U3") (pin "V11") (pinfunction "EP.VSS_EP_V11") (pintype "passive"))
      (node (ref "U3") (pin "V12") (pinfunction "EP.VSS_EP_V12") (pintype "passive"))
      (node (ref "U3") (pin "V13") (pinfunction "EP.VSS_EP_V13") (pintype "passive"))
      (node (ref "U3") (pin "V14") (pinfunction "EP.VSS_EP_V14") (pintype "passive"))
      (node (ref "U3") (pin "V15") (pinfunction "EP.VSS_EP_V15") (pintype "passive"))
      (node (ref "U3") (pin "V16") (pinfunction "EP.VSS_EP_V16") (pintype "passive"))
      (node (ref "U3") (pin "V17") (pinfunction "EP.VSS_EP_V17") (pintype "passive"))
      (node (ref "U3") (pin "V18") (pinfunction "EP.VSS_EP_V18") (pintype "passive"))
      (node (ref "U3") (pin "V19") (pinfunction "EP.VSS_EP_V19") (pintype "passive"))
      (node (ref "U3") (pin "V2") (pinfunction "EP.VSS_EP_V2") (pintype "passive"))
      (node (ref "U3") (pin "V20") (pinfunction "EP.VSS_EP_V20") (pintype "passive"))
      (node (ref "U3") (pin "V21") (pinfunction "EP.VSS_EP_V21") (pintype "passive"))
      (node (ref "U3") (pin "V22") (pinfunction "EP.VSS_EP_V22") (pintype "passive"))
      (node (ref "U3") (pin "V23") (pinfunction "EP.VSS_EP_V23") (pintype "passive"))
      (node (ref "U3") (pin "V24") (pinfunction "EP.VSS_EP_V24") (pintype "passive"))
      (node (ref "U3") (pin "V25") (pinfunction "EP.VSS_EP_V25") (pintype "passive"))
      (node (ref "U3") (pin "V3") (pinfunction "EP.VSS_EP_V3") (pintype "passive"))
      (node (ref "U3") (pin "V4") (pinfunction "EP.VSS_EP_V4") (pintype "passive"))
      (node (ref "U3") (pin "V5") (pinfunction "EP.VSS_EP_V5") (pintype "passive"))
      (node (ref "U3") (pin "V6") (pinfunction "EP.VSS_EP_V6") (pintype "passive"))
      (node (ref "U3") (pin "V7") (pinfunction "EP.VSS_EP_V7") (pintype "passive"))
      (node (ref "U3") (pin "V8") (pinfunction "EP.VSS_EP_V8") (pintype "passive"))
      (node (ref "U3") (pin "V9") (pinfunction "EP.VSS_EP_V9") (pintype "passive"))
      (node (ref "U5") (pin "23") (pinfunction "EPAD_23") (pintype "passive"))
    )
    (net (code "15") (name "Net-(CLFB-Pad2)") (class "Default")
      (node (ref "CLFB") (pin "2") (pinfunction "2_2") (pintype "passive"))
      (node (ref "CLRFB") (pin "1") (pinfunction "1_1") (pintype "passive"))
      (node (ref "RLBST") (pin "2") (pinfunction "2_2") (pintype "passive"))
    )
    (net (code "16") (name "Net-(IN-Pad2)") (class "Default")
      (node (ref "IN") (pin "2") (pinfunction "2_2") (pintype "passive"))
      (node (ref "R11I") (pin "1") (pinfunction "1_1") (pintype "passive"))
    )
    (net (code "17") (name "Net-(IN-Pad3)") (class "Default")
      (node (ref "IN") (pin "3") (pinfunction "3_3") (pintype "passive"))
      (node (ref "R10I") (pin "1") (pinfunction "1_1") (pintype "passive"))
    )
    (net (code "18") (name "Net-(R1-Pad1)") (class "Default")
      (node (ref "R1") (pin "1") (pinfunction "1_1") (pintype "passive"))
      (node (ref "R11") (pin "2") (pinfunction "2_2") (pintype "passive"))
    )
    (net (code "19") (name "Net-(REN-Pad1)") (class "Default")
      (node (ref "REN") (pin "1") (pinfunction "1_1") (pintype "passive"))
      (node (ref "RENB") (pin "2") (pinfunction "2_2") (pintype "passive"))
      (node (ref "RENT") (pin "2") (pinfunction "2_2") (pintype "passive"))
    )
    (net (code "20") (name "Net-(U3-6.OUTSCK)") (class "Default")
      (node (ref "OUT") (pin "4") (pinfunction "4_4") (pintype "passive"))
      (node (ref "U3") (pin "6") (pinfunction "6.OUTSCK_6") (pintype "input"))
    )
    (net (code "21") (name "Net-(U3-7.OUTMOSI)") (class "Default")
      (node (ref "OUT") (pin "3") (pinfunction "3_3") (pintype "passive"))
      (node (ref "U3") (pin "7") (pinfunction "7.OUTMOSI_7") (pintype "output"))
    )
    (net (code "22") (name "Net-(U3-8.OUTMISO)") (class "Default")
      (node (ref "OUT") (pin "2") (pinfunction "2_2") (pintype "passive"))
      (node (ref "U3") (pin "8") (pinfunction "8.OUTMISO_8") (pintype "output"))
    )
    (net (code "23") (name "Net-(U5-EN)") (class "Default")
      (node (ref "REN") (pin "2") (pinfunction "2_2") (pintype "passive"))
      (node (ref "U5") (pin "2") (pinfunction "EN_2") (pintype "input"))
    )
    (net (code "24") (name "Net-(U5-LL)") (class "Default")
      (node (ref "CBST") (pin "2") (pinfunction "2_2") (pintype "passive"))
      (node (ref "L2") (pin "2") (pinfunction "2_2") (pintype "passive"))
      (node (ref "RLBST") (pin "1") (pinfunction "1_1") (pintype "passive"))
      (node (ref "U5") (pin "10") (pinfunction "LL_6_10") (pintype "output"))
      (node (ref "U5") (pin "11") (pinfunction "LL_11") (pintype "output"))
      (node (ref "U5") (pin "6") (pinfunction "LL_2_6") (pintype "output"))
      (node (ref "U5") (pin "7") (pinfunction "LL_3_7") (pintype "output"))
      (node (ref "U5") (pin "8") (pinfunction "LL_4_8") (pintype "output"))
      (node (ref "U5") (pin "9") (pinfunction "LL_5_9") (pintype "output"))
    )
    (net (code "25") (name "Net-(U5-MODE)") (class "Default")
      (node (ref "RMODEG") (pin "2") (pinfunction "2_2") (pintype "passive"))
      (node (ref "U5") (pin "20") (pinfunction "MODE_20") (pintype "input"))
    )
    (net (code "26") (name "Net-(U5-PGOOD)") (class "Default")
      (node (ref "RPG") (pin "1") (pinfunction "1_1") (pintype "passive"))
      (node (ref "U5") (pin "3") (pinfunction "PGOOD_3") (pintype "output"))
    )
    (net (code "27") (name "Net-(U5-TRIP)") (class "Default")
      (node (ref "TRIP") (pin "2") (pinfunction "2_2") (pintype "passive"))
      (node (ref "U5") (pin "21") (pinfunction "TRIP_21") (pintype "input"))
    )
    (net (code "28") (name "Net-(U5-VBST)") (class "Default")
      (node (ref "CBST") (pin "1") (pinfunction "1_1") (pintype "passive"))
      (node (ref "U5") (pin "4") (pinfunction "VBST_4") (pintype "input"))
    )
    (net (code "29") (name "Net-(U5-VFB)") (class "Default")
      (node (ref "CLRFB") (pin "2") (pinfunction "2_2") (pintype "passive"))
      (node (ref "R1") (pin "2") (pinfunction "2_2") (pintype "passive"))
      (node (ref "R2") (pin "1") (pinfunction "1_1") (pintype "passive"))
      (node (ref "U5") (pin "1") (pinfunction "VFB_1") (pintype "output"))
    )
    (net (code "30") (name "Net-(U5-VREG)") (class "Default")
      (node (ref "CVREG") (pin "1") (pinfunction "1_1") (pintype "passive"))
      (node (ref "RPG") (pin "2") (pinfunction "2_2") (pintype "passive"))
      (node (ref "U5") (pin "18") (pinfunction "VREG_18") (pintype "power_in"))
    )
    (net (code "31") (name "VCCINT") (class "Default")
      (node (ref "CIN") (pin "1") (pinfunction "1_1") (pintype "passive"))
      (node (ref "CVIN") (pin "+") (pinfunction "+_+") (pintype "passive"))
      (node (ref "JIN") (pin "1") (pinfunction "1_1") (pintype "passive"))
      (node (ref "RENT") (pin "1") (pinfunction "1_1") (pintype "passive"))
      (node (ref "U5") (pin "12") (pinfunction "VIN_2_12") (pintype "input"))
      (node (ref "U5") (pin "13") (pinfunction "VIN_3_13") (pintype "input"))
      (node (ref "U5") (pin "14") (pinfunction "VIN_4_14") (pintype "input"))
      (node (ref "U5") (pin "15") (pinfunction "VIN_5_15") (pintype "input"))
      (node (ref "U5") (pin "16") (pinfunction "VIN_6_16") (pintype "input"))
      (node (ref "U5") (pin "17") (pinfunction "VIN_17") (pintype "input"))
      (node (ref "U5") (pin "19") (pinfunction "VDD_19") (pintype "power_in"))
    )
    (net (code "32") (name "VCC_0V9") (class "Default")
      (node (ref "0V9") (pin "1") (pinfunction "P$1_1") (pintype "passive"))
      (node (ref "C10D") (pin "1") (pinfunction "1_1") (pintype "passive"))
      (node (ref "C10D1") (pin "1") (pinfunction "1_1") (pintype "passive"))
      (node (ref "C10D2") (pin "1") (pinfunction "1_1") (pintype "passive"))
      (node (ref "C10D3") (pin "1") (pinfunction "1_1") (pintype "passive"))
      (node (ref "C11D") (pin "1") (pinfunction "1_1") (pintype "passive"))
      (node (ref "C11D1") (pin "1") (pinfunction "1_1") (pintype "passive"))
      (node (ref "C11D2") (pin "1") (pinfunction "1_1") (pintype "passive"))
      (node (ref "C11D3") (pin "1") (pinfunction "1_1") (pintype "passive"))
      (node (ref "C12D") (pin "1") (pinfunction "1_1") (pintype "passive"))
      (node (ref "C12D1") (pin "1") (pinfunction "1_1") (pintype "passive"))
      (node (ref "C12D2") (pin "1") (pinfunction "1_1") (pintype "passive"))
      (node (ref "C12D3") (pin "1") (pinfunction "1_1") (pintype "passive"))
      (node (ref "C13D") (pin "1") (pinfunction "1_1") (pintype "passive"))
      (node (ref "C13D1") (pin "1") (pinfunction "1_1") (pintype "passive"))
      (node (ref "C13D2") (pin "1") (pinfunction "1_1") (pintype "passive"))
      (node (ref "C13D3") (pin "1") (pinfunction "1_1") (pintype "passive"))
      (node (ref "C14D") (pin "1") (pinfunction "1_1") (pintype "passive"))
      (node (ref "C14D1") (pin "1") (pinfunction "1_1") (pintype "passive"))
      (node (ref "C14D2") (pin "1") (pinfunction "1_1") (pintype "passive"))
      (node (ref "C14D3") (pin "1") (pinfunction "1_1") (pintype "passive"))
      (node (ref "C15D") (pin "1") (pinfunction "1_1") (pintype "passive"))
      (node (ref "C15D1") (pin "1") (pinfunction "1_1") (pintype "passive"))
      (node (ref "C15D2") (pin "1") (pinfunction "1_1") (pintype "passive"))
      (node (ref "C15D3") (pin "1") (pinfunction "1_1") (pintype "passive"))
      (node (ref "C16D") (pin "1") (pinfunction "1_1") (pintype "passive"))
      (node (ref "C16D1") (pin "1") (pinfunction "1_1") (pintype "passive"))
      (node (ref "C16D2") (pin "1") (pinfunction "1_1") (pintype "passive"))
      (node (ref "C16D3") (pin "1") (pinfunction "1_1") (pintype "passive"))
      (node (ref "C17D") (pin "1") (pinfunction "1_1") (pintype "passive"))
      (node (ref "C17D1") (pin "1") (pinfunction "1_1") (pintype "passive"))
      (node (ref "C17D2") (pin "1") (pinfunction "1_1") (pintype "passive"))
      (node (ref "C17D3") (pin "1") (pinfunction "1_1") (pintype "passive"))
      (node (ref "C18D") (pin "1") (pinfunction "1_1") (pintype "passive"))
      (node (ref "C18D1") (pin "1") (pinfunction "1_1") (pintype "passive"))
      (node (ref "C18D2") (pin "1") (pinfunction "1_1") (pintype "passive"))
      (node (ref "C18D3") (pin "1") (pinfunction "1_1") (pintype "passive"))
      (node (ref "C19D") (pin "1") (pinfunction "1_1") (pintype "passive"))
      (node (ref "C19D1") (pin "1") (pinfunction "1_1") (pintype "passive"))
      (node (ref "C19D2") (pin "1") (pinfunction "1_1") (pintype "passive"))
      (node (ref "C19D3") (pin "1") (pinfunction "1_1") (pintype "passive"))
      (node (ref "C1AD") (pin "1") (pinfunction "1_1") (pintype "passive"))
      (node (ref "C1AD1") (pin "1") (pinfunction "1_1") (pintype "passive"))
      (node (ref "C1AD2") (pin "1") (pinfunction "1_1") (pintype "passive"))
      (node (ref "C1AD3") (pin "1") (pinfunction "1_1") (pintype "passive"))
      (node (ref "C1BD") (pin "1") (pinfunction "1_1") (pintype "passive"))
      (node (ref "C1BD1") (pin "1") (pinfunction "1_1") (pintype "passive"))
      (node (ref "C1BD2") (pin "1") (pinfunction "1_1") (pintype "passive"))
      (node (ref "C1BD3") (pin "1") (pinfunction "1_1") (pintype "passive"))
      (node (ref "C1CD") (pin "1") (pinfunction "1_1") (pintype "passive"))
      (node (ref "C1CD1") (pin "1") (pinfunction "1_1") (pintype "passive"))
      (node (ref "C1CD2") (pin "1") (pinfunction "1_1") (pintype "passive"))
      (node (ref "C1CD3") (pin "1") (pinfunction "1_1") (pintype "passive"))
      (node (ref "C1DD") (pin "1") (pinfunction "1_1") (pintype "passive"))
      (node (ref "C1DD1") (pin "1") (pinfunction "1_1") (pintype "passive"))
      (node (ref "C1DD2") (pin "1") (pinfunction "1_1") (pintype "passive"))
      (node (ref "C1DD3") (pin "1") (pinfunction "1_1") (pintype "passive"))
      (node (ref "C1ED") (pin "1") (pinfunction "1_1") (pintype "passive"))
      (node (ref "C1ED1") (pin "1") (pinfunction "1_1") (pintype "passive"))
      (node (ref "C1ED2") (pin "1") (pinfunction "1_1") (pintype "passive"))
      (node (ref "C1ED3") (pin "1") (pinfunction "1_1") (pintype "passive"))
      (node (ref "CLFB") (pin "1") (pinfunction "1_1") (pintype "passive"))
      (node (ref "COUT") (pin "1") (pinfunction "1_1") (pintype "passive"))
      (node (ref "CT1") (pin "1") (pinfunction "1_1") (pintype "passive"))
      (node (ref "CT2") (pin "1") (pinfunction "1_1") (pintype "passive"))
      (node (ref "CT3") (pin "1") (pinfunction "1_1") (pintype "passive"))
      (node (ref "CT4") (pin "1") (pinfunction "1_1") (pintype "passive"))
      (node (ref "CT5") (pin "1") (pinfunction "1_1") (pintype "passive"))
      (node (ref "CT6") (pin "1") (pinfunction "1_1") (pintype "passive"))
      (node (ref "L2") (pin "1") (pinfunction "1_1") (pintype "passive"))
      (node (ref "R11") (pin "1") (pinfunction "1_1") (pintype "passive"))
      (node (ref "U0") (pin "13") (pinfunction "13.IOREF_13") (pintype "passive"))
      (node (ref "U0") (pin "14") (pinfunction "14.VDD_14") (pintype "passive"))
      (node (ref "U0") (pin "15") (pinfunction "15.VDD_15") (pintype "passive"))
      (node (ref "U0") (pin "16") (pinfunction "16.VDD_16") (pintype "passive"))
      (node (ref "U0") (pin "17") (pinfunction "17.VDD_17") (pintype "passive"))
      (node (ref "U0") (pin "18") (pinfunction "18.VDD_18") (pintype "passive"))
      (node (ref "U0") (pin "19") (pinfunction "19.VDD_19") (pintype "passive"))
      (node (ref "U0") (pin "20") (pinfunction "20.VDD_20") (pintype "passive"))
      (node (ref "U0") (pin "21") (pinfunction "21.VDD_21") (pintype "passive"))
      (node (ref "U0") (pin "22") (pinfunction "22.VDD_22") (pintype "passive"))
      (node (ref "U0") (pin "23") (pinfunction "23.VDD_23") (pintype "passive"))
      (node (ref "U0") (pin "24") (pinfunction "24.VDD_24") (pintype "passive"))
      (node (ref "U0") (pin "25") (pinfunction "25.VDD_25") (pintype "passive"))
      (node (ref "U0") (pin "26") (pinfunction "26.VDD_26") (pintype "passive"))
      (node (ref "U0") (pin "27") (pinfunction "27.VDD_27") (pintype "passive"))
      (node (ref "U0") (pin "28") (pinfunction "28.VDD_28") (pintype "passive"))
      (node (ref "U0") (pin "29") (pinfunction "29.VDD_29") (pintype "passive"))
      (node (ref "U0") (pin "30") (pinfunction "30.VDD_30") (pintype "passive"))
      (node (ref "U0") (pin "31") (pinfunction "31.VDD_31") (pintype "passive"))
      (node (ref "U0") (pin "32") (pinfunction "32.VDD_32") (pintype "passive"))
      (node (ref "U0") (pin "33") (pinfunction "33.VDD_33") (pintype "passive"))
      (node (ref "U0") (pin "34") (pinfunction "34.VDD_34") (pintype "passive"))
      (node (ref "U0") (pin "35") (pinfunction "35.VDD_35") (pintype "passive"))
      (node (ref "U0") (pin "36") (pinfunction "36.VDD_36") (pintype "passive"))
      (node (ref "U0") (pin "37") (pinfunction "37.VDD_37") (pintype "passive"))
      (node (ref "U0") (pin "38") (pinfunction "38.VDD_38") (pintype "passive"))
      (node (ref "U0") (pin "39") (pinfunction "39.VDD_39") (pintype "passive"))
      (node (ref "U0") (pin "40") (pinfunction "40.VDD_40") (pintype "passive"))
      (node (ref "U0") (pin "41") (pinfunction "41.VDD_41") (pintype "passive"))
      (node (ref "U0") (pin "42") (pinfunction "42.VDD_42") (pintype "passive"))
      (node (ref "U0") (pin "43") (pinfunction "43.VDD_43") (pintype "passive"))
      (node (ref "U0") (pin "44") (pinfunction "44.VDD_44") (pintype "passive"))
      (node (ref "U0") (pin "45") (pinfunction "45.VDD_45") (pintype "passive"))
      (node (ref "U0") (pin "46") (pinfunction "46.VDD_46") (pintype "passive"))
      (node (ref "U0") (pin "47") (pinfunction "47.VDD_47") (pintype "passive"))
      (node (ref "U0") (pin "48") (pinfunction "48.VDD_48") (pintype "passive"))
      (node (ref "U1") (pin "13") (pinfunction "13.IOREF_13") (pintype "passive"))
      (node (ref "U1") (pin "14") (pinfunction "14.VDD_14") (pintype "passive"))
      (node (ref "U1") (pin "15") (pinfunction "15.VDD_15") (pintype "passive"))
      (node (ref "U1") (pin "16") (pinfunction "16.VDD_16") (pintype "passive"))
      (node (ref "U1") (pin "17") (pinfunction "17.VDD_17") (pintype "passive"))
      (node (ref "U1") (pin "18") (pinfunction "18.VDD_18") (pintype "passive"))
      (node (ref "U1") (pin "19") (pinfunction "19.VDD_19") (pintype "passive"))
      (node (ref "U1") (pin "20") (pinfunction "20.VDD_20") (pintype "passive"))
      (node (ref "U1") (pin "21") (pinfunction "21.VDD_21") (pintype "passive"))
      (node (ref "U1") (pin "22") (pinfunction "22.VDD_22") (pintype "passive"))
      (node (ref "U1") (pin "23") (pinfunction "23.VDD_23") (pintype "passive"))
      (node (ref "U1") (pin "24") (pinfunction "24.VDD_24") (pintype "passive"))
      (node (ref "U1") (pin "25") (pinfunction "25.VDD_25") (pintype "passive"))
      (node (ref "U1") (pin "26") (pinfunction "26.VDD_26") (pintype "passive"))
      (node (ref "U1") (pin "27") (pinfunction "27.VDD_27") (pintype "passive"))
      (node (ref "U1") (pin "28") (pinfunction "28.VDD_28") (pintype "passive"))
      (node (ref "U1") (pin "29") (pinfunction "29.VDD_29") (pintype "passive"))
      (node (ref "U1") (pin "30") (pinfunction "30.VDD_30") (pintype "passive"))
      (node (ref "U1") (pin "31") (pinfunction "31.VDD_31") (pintype "passive"))
      (node (ref "U1") (pin "32") (pinfunction "32.VDD_32") (pintype "passive"))
      (node (ref "U1") (pin "33") (pinfunction "33.VDD_33") (pintype "passive"))
      (node (ref "U1") (pin "34") (pinfunction "34.VDD_34") (pintype "passive"))
      (node (ref "U1") (pin "35") (pinfunction "35.VDD_35") (pintype "passive"))
      (node (ref "U1") (pin "36") (pinfunction "36.VDD_36") (pintype "passive"))
      (node (ref "U1") (pin "37") (pinfunction "37.VDD_37") (pintype "passive"))
      (node (ref "U1") (pin "38") (pinfunction "38.VDD_38") (pintype "passive"))
      (node (ref "U1") (pin "39") (pinfunction "39.VDD_39") (pintype "passive"))
      (node (ref "U1") (pin "40") (pinfunction "40.VDD_40") (pintype "passive"))
      (node (ref "U1") (pin "41") (pinfunction "41.VDD_41") (pintype "passive"))
      (node (ref "U1") (pin "42") (pinfunction "42.VDD_42") (pintype "passive"))
      (node (ref "U1") (pin "43") (pinfunction "43.VDD_43") (pintype "passive"))
      (node (ref "U1") (pin "44") (pinfunction "44.VDD_44") (pintype "passive"))
      (node (ref "U1") (pin "45") (pinfunction "45.VDD_45") (pintype "passive"))
      (node (ref "U1") (pin "46") (pinfunction "46.VDD_46") (pintype "passive"))
      (node (ref "U1") (pin "47") (pinfunction "47.VDD_47") (pintype "passive"))
      (node (ref "U1") (pin "48") (pinfunction "48.VDD_48") (pintype "passive"))
      (node (ref "U2") (pin "13") (pinfunction "13.IOREF_13") (pintype "passive"))
      (node (ref "U2") (pin "14") (pinfunction "14.VDD_14") (pintype "passive"))
      (node (ref "U2") (pin "15") (pinfunction "15.VDD_15") (pintype "passive"))
      (node (ref "U2") (pin "16") (pinfunction "16.VDD_16") (pintype "passive"))
      (node (ref "U2") (pin "17") (pinfunction "17.VDD_17") (pintype "passive"))
      (node (ref "U2") (pin "18") (pinfunction "18.VDD_18") (pintype "passive"))
      (node (ref "U2") (pin "19") (pinfunction "19.VDD_19") (pintype "passive"))
      (node (ref "U2") (pin "20") (pinfunction "20.VDD_20") (pintype "passive"))
      (node (ref "U2") (pin "21") (pinfunction "21.VDD_21") (pintype "passive"))
      (node (ref "U2") (pin "22") (pinfunction "22.VDD_22") (pintype "passive"))
      (node (ref "U2") (pin "23") (pinfunction "23.VDD_23") (pintype "passive"))
      (node (ref "U2") (pin "24") (pinfunction "24.VDD_24") (pintype "passive"))
      (node (ref "U2") (pin "25") (pinfunction "25.VDD_25") (pintype "passive"))
      (node (ref "U2") (pin "26") (pinfunction "26.VDD_26") (pintype "passive"))
      (node (ref "U2") (pin "27") (pinfunction "27.VDD_27") (pintype "passive"))
      (node (ref "U2") (pin "28") (pinfunction "28.VDD_28") (pintype "passive"))
      (node (ref "U2") (pin "29") (pinfunction "29.VDD_29") (pintype "passive"))
      (node (ref "U2") (pin "30") (pinfunction "30.VDD_30") (pintype "passive"))
      (node (ref "U2") (pin "31") (pinfunction "31.VDD_31") (pintype "passive"))
      (node (ref "U2") (pin "32") (pinfunction "32.VDD_32") (pintype "passive"))
      (node (ref "U2") (pin "33") (pinfunction "33.VDD_33") (pintype "passive"))
      (node (ref "U2") (pin "34") (pinfunction "34.VDD_34") (pintype "passive"))
      (node (ref "U2") (pin "35") (pinfunction "35.VDD_35") (pintype "passive"))
      (node (ref "U2") (pin "36") (pinfunction "36.VDD_36") (pintype "passive"))
      (node (ref "U2") (pin "37") (pinfunction "37.VDD_37") (pintype "passive"))
      (node (ref "U2") (pin "38") (pinfunction "38.VDD_38") (pintype "passive"))
      (node (ref "U2") (pin "39") (pinfunction "39.VDD_39") (pintype "passive"))
      (node (ref "U2") (pin "40") (pinfunction "40.VDD_40") (pintype "passive"))
      (node (ref "U2") (pin "41") (pinfunction "41.VDD_41") (pintype "passive"))
      (node (ref "U2") (pin "42") (pinfunction "42.VDD_42") (pintype "passive"))
      (node (ref "U2") (pin "43") (pinfunction "43.VDD_43") (pintype "passive"))
      (node (ref "U2") (pin "44") (pinfunction "44.VDD_44") (pintype "passive"))
      (node (ref "U2") (pin "45") (pinfunction "45.VDD_45") (pintype "passive"))
      (node (ref "U2") (pin "46") (pinfunction "46.VDD_46") (pintype "passive"))
      (node (ref "U2") (pin "47") (pinfunction "47.VDD_47") (pintype "passive"))
      (node (ref "U2") (pin "48") (pinfunction "48.VDD_48") (pintype "passive"))
      (node (ref "U3") (pin "13") (pinfunction "13.IOREF_13") (pintype "passive"))
      (node (ref "U3") (pin "14") (pinfunction "14.VDD_14") (pintype "passive"))
      (node (ref "U3") (pin "15") (pinfunction "15.VDD_15") (pintype "passive"))
      (node (ref "U3") (pin "16") (pinfunction "16.VDD_16") (pintype "passive"))
      (node (ref "U3") (pin "17") (pinfunction "17.VDD_17") (pintype "passive"))
      (node (ref "U3") (pin "18") (pinfunction "18.VDD_18") (pintype "passive"))
      (node (ref "U3") (pin "19") (pinfunction "19.VDD_19") (pintype "passive"))
      (node (ref "U3") (pin "20") (pinfunction "20.VDD_20") (pintype "passive"))
      (node (ref "U3") (pin "21") (pinfunction "21.VDD_21") (pintype "passive"))
      (node (ref "U3") (pin "22") (pinfunction "22.VDD_22") (pintype "passive"))
      (node (ref "U3") (pin "23") (pinfunction "23.VDD_23") (pintype "passive"))
      (node (ref "U3") (pin "24") (pinfunction "24.VDD_24") (pintype "passive"))
      (node (ref "U3") (pin "25") (pinfunction "25.VDD_25") (pintype "passive"))
      (node (ref "U3") (pin "26") (pinfunction "26.VDD_26") (pintype "passive"))
      (node (ref "U3") (pin "27") (pinfunction "27.VDD_27") (pintype "passive"))
      (node (ref "U3") (pin "28") (pinfunction "28.VDD_28") (pintype "passive"))
      (node (ref "U3") (pin "29") (pinfunction "29.VDD_29") (pintype "passive"))
      (node (ref "U3") (pin "30") (pinfunction "30.VDD_30") (pintype "passive"))
      (node (ref "U3") (pin "31") (pinfunction "31.VDD_31") (pintype "passive"))
      (node (ref "U3") (pin "32") (pinfunction "32.VDD_32") (pintype "passive"))
      (node (ref "U3") (pin "33") (pinfunction "33.VDD_33") (pintype "passive"))
      (node (ref "U3") (pin "34") (pinfunction "34.VDD_34") (pintype "passive"))
      (node (ref "U3") (pin "35") (pinfunction "35.VDD_35") (pintype "passive"))
      (node (ref "U3") (pin "36") (pinfunction "36.VDD_36") (pintype "passive"))
      (node (ref "U3") (pin "37") (pinfunction "37.VDD_37") (pintype "passive"))
      (node (ref "U3") (pin "38") (pinfunction "38.VDD_38") (pintype "passive"))
      (node (ref "U3") (pin "39") (pinfunction "39.VDD_39") (pintype "passive"))
      (node (ref "U3") (pin "40") (pinfunction "40.VDD_40") (pintype "passive"))
      (node (ref "U3") (pin "41") (pinfunction "41.VDD_41") (pintype "passive"))
      (node (ref "U3") (pin "42") (pinfunction "42.VDD_42") (pintype "passive"))
      (node (ref "U3") (pin "43") (pinfunction "43.VDD_43") (pintype "passive"))
      (node (ref "U3") (pin "44") (pinfunction "44.VDD_44") (pintype "passive"))
      (node (ref "U3") (pin "45") (pinfunction "45.VDD_45") (pintype "passive"))
      (node (ref "U3") (pin "46") (pinfunction "46.VDD_46") (pintype "passive"))
      (node (ref "U3") (pin "47") (pinfunction "47.VDD_47") (pintype "passive"))
      (node (ref "U3") (pin "48") (pinfunction "48.VDD_48") (pintype "passive"))
    )
    (net (code "33") (name "VCC_1V8") (class "Default")
      (node (ref "C02") (pin "1") (pinfunction "1_1") (pintype "passive"))
      (node (ref "RG01") (pin "2") (pinfunction "2.OUT_2") (pintype "passive"))
      (node (ref "U0") (pin "4") (pinfunction "4.VDD_IO_4") (pintype "passive"))
      (node (ref "U1") (pin "4") (pinfunction "4.VDD_IO_4") (pintype "passive"))
      (node (ref "U10B") (pin "1") (pinfunction "1.VCC1_1") (pintype "passive"))
      (node (ref "U2") (pin "4") (pinfunction "4.VDD_IO_4") (pintype "passive"))
      (node (ref "U3") (pin "4") (pinfunction "4.VDD_IO_4") (pintype "passive"))
    )
    (net (code "34") (name "VCC_3V3") (class "Default")
      (node (ref "3V3") (pin "1") (pinfunction "P$1_1") (pintype "passive"))
      (node (ref "C01") (pin "1") (pinfunction "1_1") (pintype "passive"))
      (node (ref "IN") (pin "5") (pinfunction "5_5") (pintype "passive"))
      (node (ref "OUT") (pin "1") (pinfunction "1_1") (pintype "passive"))
      (node (ref "RG01") (pin "1") (pinfunction "1.IN_1") (pintype "passive"))
      (node (ref "U10B") (pin "5") (pinfunction "5.VCC_5") (pintype "passive"))
    )
    (net (code "35") (name "unconnected-(JIN-Pad2)") (class "Default")
      (node (ref "JIN") (pin "2") (pinfunction "2_2") (pintype "passive"))
    )
    (net (code "36") (name "unconnected-(U0-5.OUTCLK-Pad5)") (class "Default")
      (node (ref "U0") (pin "5") (pinfunction "5.OUTCLK_5") (pintype "output"))
    )
    (net (code "37") (name "unconnected-(U1-5.OUTCLK-Pad5)") (class "Default")
      (node (ref "U1") (pin "5") (pinfunction "5.OUTCLK_5") (pintype "output"))
    )
    (net (code "38") (name "unconnected-(U2-5.OUTCLK-Pad5)") (class "Default")
      (node (ref "U2") (pin "5") (pinfunction "5.OUTCLK_5") (pintype "output"))
    )
    (net (code "39") (name "unconnected-(U3-5.OUTCLK-Pad5)") (class "Default")
      (node (ref "U3") (pin "5") (pinfunction "5.OUTCLK_5") (pintype "output"))
    )
    (net (code "40") (name "unconnected-(U5-N{slash}C-Pad5)") (class "Default")
      (node (ref "U5") (pin "5") (pinfunction "N/C_5") (pintype "passive"))
    )
    (net (code "41") (name "unconnected-(U5-RF-Pad22)") (class "Default")
      (node (ref "U5") (pin "22") (pinfunction "RF_22") (pintype "input"))
    )
  )
)
